# 7seg157.net
KiCad netlist of a schematic drawn in EAGLE
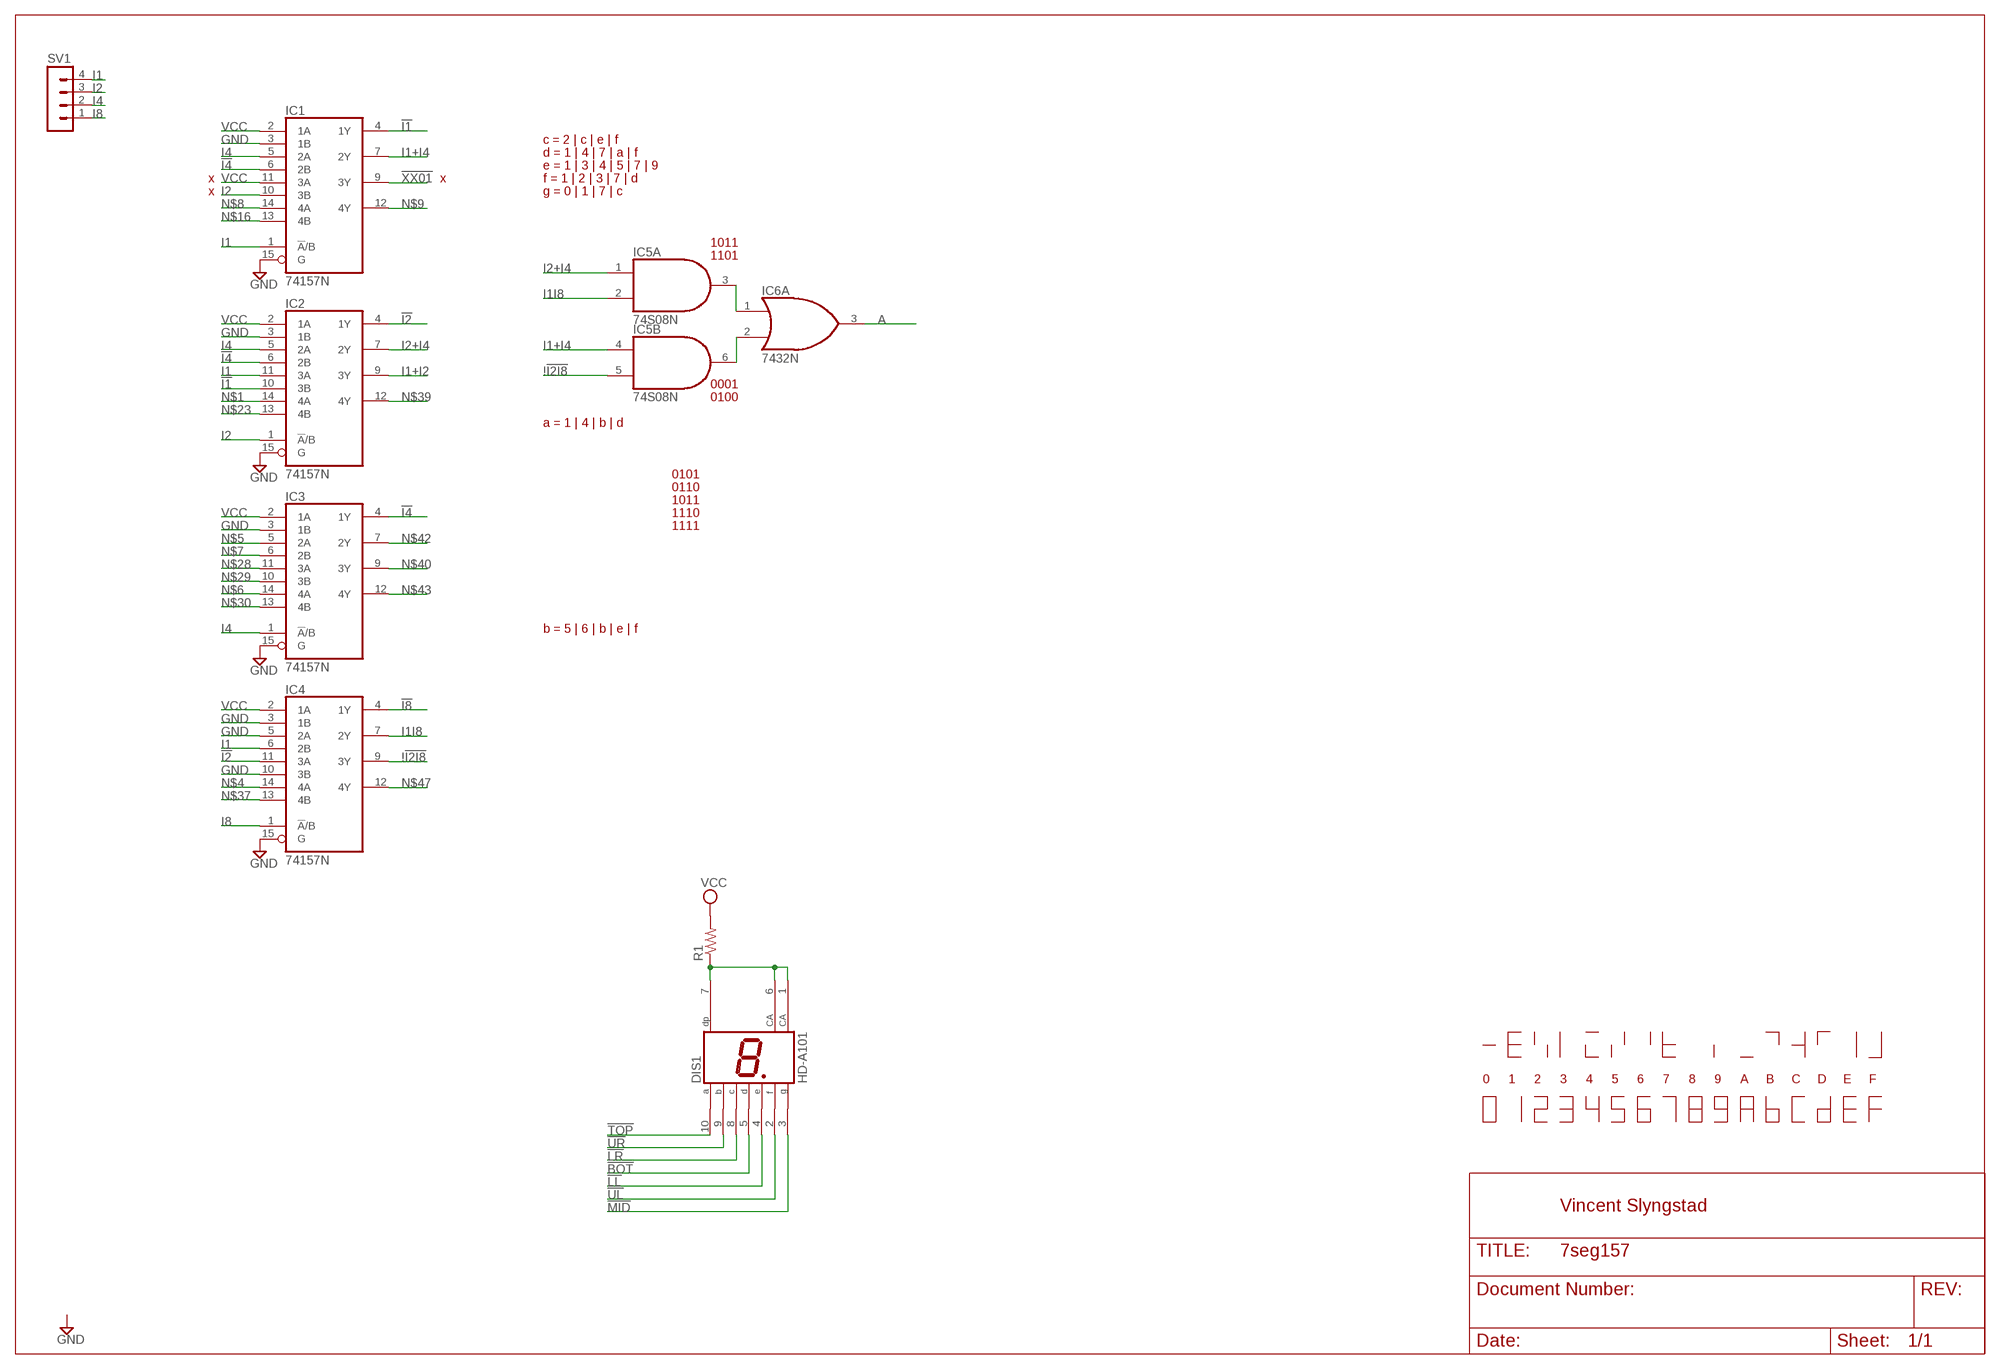
[diagram p0: schematic, sheet 1]

(export (version "E")
  (design (tool "Eeschema 10.0.6"))
  (components
    (comp (ref "DIS1")
      (value "HD-A101")
      (footprint "eagle-import:HDSP-A")
      (libsource (lib "eagle-import") (part "HD-A101"))
    )
    (comp (ref "IC1")
      (value "74157N")
      (footprint "eagle-import:DIL16")
      (libsource (lib "eagle-import") (part "74157N"))
    )
    (comp (ref "IC2")
      (value "74157N")
      (footprint "eagle-import:DIL16")
      (libsource (lib "eagle-import") (part "74157N"))
    )
    (comp (ref "IC3")
      (value "74157N")
      (footprint "eagle-import:DIL16")
      (libsource (lib "eagle-import") (part "74157N"))
    )
    (comp (ref "IC4")
      (value "74157N")
      (footprint "eagle-import:DIL16")
      (libsource (lib "eagle-import") (part "74157N"))
    )
    (comp (ref "IC5")
      (value "74S08N")
      (footprint "eagle-import:DIL14")
      (libsource (lib "eagle-import") (part "7408NS"))
    )
    (comp (ref "IC6")
      (value "7432N")
      (footprint "eagle-import:DIL14")
      (libsource (lib "eagle-import") (part "7432N"))
    )
    (comp (ref "R1")
      (value "R-US_0207/10")
      (footprint "eagle-import:0207_10")
      (libsource (lib "eagle-import") (part "R-US_0207/10"))
    )
    (comp (ref "SV1")
      (value "MA04-1")
      (footprint "eagle-import:MA04-1")
      (libsource (lib "eagle-import") (part "MA04-1"))
    )
  )
  (nets
    (net (code "1") (name "/A") (class "Default")
      (node (ref "IC6") (pin "3") (pinfunction "O_3") (pintype "output"))
    )
    (net (code "2") (name "/I1") (class "Default")
      (node (ref "IC1") (pin "1") (pinfunction "~{A}/B_1") (pintype "input"))
      (node (ref "IC2") (pin "11") (pinfunction "3A_11") (pintype "input"))
      (node (ref "IC4") (pin "6") (pinfunction "2B_6") (pintype "input"))
      (node (ref "SV1") (pin "4") (pinfunction "4_4") (pintype "passive"))
    )
    (net (code "3") (name "/I1+I2") (class "Default")
      (node (ref "IC2") (pin "9") (pinfunction "3Y_9") (pintype "output"))
    )
    (net (code "4") (name "/I1+I4") (class "Default")
      (node (ref "IC1") (pin "7") (pinfunction "2Y_7") (pintype "output"))
      (node (ref "IC5") (pin "4") (pinfunction "I0_4") (pintype "input"))
    )
    (net (code "5") (name "/I1I8") (class "Default")
      (node (ref "IC4") (pin "7") (pinfunction "2Y_7") (pintype "output"))
      (node (ref "IC5") (pin "2") (pinfunction "I1_2") (pintype "input"))
    )
    (net (code "6") (name "/I2") (class "Default")
      (node (ref "IC1") (pin "10") (pinfunction "3B_10") (pintype "input"))
      (node (ref "IC2") (pin "1") (pinfunction "~{A}/B_1") (pintype "input"))
      (node (ref "SV1") (pin "3") (pinfunction "3_3") (pintype "passive"))
    )
    (net (code "7") (name "/I2+I4") (class "Default")
      (node (ref "IC2") (pin "7") (pinfunction "2Y_7") (pintype "output"))
      (node (ref "IC5") (pin "1") (pinfunction "I0_1") (pintype "input"))
    )
    (net (code "8") (name "/I4") (class "Default")
      (node (ref "IC1") (pin "5") (pinfunction "2A_5") (pintype "input"))
      (node (ref "IC2") (pin "5") (pinfunction "2A_5") (pintype "input"))
      (node (ref "IC3") (pin "1") (pinfunction "~{A}/B_1") (pintype "input"))
      (node (ref "SV1") (pin "2") (pinfunction "2_2") (pintype "passive"))
    )
    (net (code "9") (name "/I8") (class "Default")
      (node (ref "IC4") (pin "1") (pinfunction "~{A}/B_1") (pintype "input"))
      (node (ref "SV1") (pin "1") (pinfunction "1_1") (pintype "passive"))
    )
    (net (code "10") (name "/N$1") (class "Default")
      (node (ref "IC2") (pin "14") (pinfunction "4A_14") (pintype "input"))
    )
    (net (code "11") (name "/N$4") (class "Default")
      (node (ref "IC4") (pin "14") (pinfunction "4A_14") (pintype "input"))
    )
    (net (code "12") (name "/N$5") (class "Default")
      (node (ref "IC3") (pin "5") (pinfunction "2A_5") (pintype "input"))
    )
    (net (code "13") (name "/N$6") (class "Default")
      (node (ref "IC3") (pin "14") (pinfunction "4A_14") (pintype "input"))
    )
    (net (code "14") (name "/N$7") (class "Default")
      (node (ref "IC3") (pin "6") (pinfunction "2B_6") (pintype "input"))
    )
    (net (code "15") (name "/N$8") (class "Default")
      (node (ref "IC1") (pin "14") (pinfunction "4A_14") (pintype "input"))
    )
    (net (code "16") (name "/N$9") (class "Default")
      (node (ref "IC1") (pin "12") (pinfunction "4Y_12") (pintype "output"))
    )
    (net (code "17") (name "/N$16") (class "Default")
      (node (ref "IC1") (pin "13") (pinfunction "4B_13") (pintype "input"))
    )
    (net (code "18") (name "/N$23") (class "Default")
      (node (ref "IC2") (pin "13") (pinfunction "4B_13") (pintype "input"))
    )
    (net (code "19") (name "/N$28") (class "Default")
      (node (ref "IC3") (pin "11") (pinfunction "3A_11") (pintype "input"))
    )
    (net (code "20") (name "/N$29") (class "Default")
      (node (ref "IC3") (pin "10") (pinfunction "3B_10") (pintype "input"))
    )
    (net (code "21") (name "/N$30") (class "Default")
      (node (ref "IC3") (pin "13") (pinfunction "4B_13") (pintype "input"))
    )
    (net (code "22") (name "/N$37") (class "Default")
      (node (ref "IC4") (pin "13") (pinfunction "4B_13") (pintype "input"))
    )
    (net (code "23") (name "/N$39") (class "Default")
      (node (ref "IC2") (pin "12") (pinfunction "4Y_12") (pintype "output"))
    )
    (net (code "24") (name "/N$40") (class "Default")
      (node (ref "IC3") (pin "9") (pinfunction "3Y_9") (pintype "output"))
    )
    (net (code "25") (name "/N$42") (class "Default")
      (node (ref "IC3") (pin "7") (pinfunction "2Y_7") (pintype "output"))
    )
    (net (code "26") (name "/N$43") (class "Default")
      (node (ref "IC3") (pin "12") (pinfunction "4Y_12") (pintype "output"))
    )
    (net (code "27") (name "/N$47") (class "Default")
      (node (ref "IC4") (pin "12") (pinfunction "4Y_12") (pintype "output"))
    )
    (net (code "28") (name "/~I2I8") (class "Default")
      (node (ref "IC4") (pin "9") (pinfunction "3Y_9") (pintype "output"))
      (node (ref "IC5") (pin "5") (pinfunction "I1_5") (pintype "input"))
    )
    (net (code "29") (name "/~{BOT}") (class "Default")
      (node (ref "DIS1") (pin "5") (pinfunction "D_5") (pintype "passive"))
    )
    (net (code "30") (name "/~{I1}") (class "Default")
      (node (ref "IC1") (pin "4") (pinfunction "1Y_4") (pintype "output"))
      (node (ref "IC2") (pin "10") (pinfunction "3B_10") (pintype "input"))
    )
    (net (code "31") (name "/~{I2}") (class "Default")
      (node (ref "IC2") (pin "4") (pinfunction "1Y_4") (pintype "output"))
      (node (ref "IC4") (pin "11") (pinfunction "3A_11") (pintype "input"))
    )
    (net (code "32") (name "/~{I4}") (class "Default")
      (node (ref "IC1") (pin "6") (pinfunction "2B_6") (pintype "input"))
      (node (ref "IC2") (pin "6") (pinfunction "2B_6") (pintype "input"))
      (node (ref "IC3") (pin "4") (pinfunction "1Y_4") (pintype "output"))
    )
    (net (code "33") (name "/~{I8}") (class "Default")
      (node (ref "IC4") (pin "4") (pinfunction "1Y_4") (pintype "output"))
    )
    (net (code "34") (name "/~{LL}") (class "Default")
      (node (ref "DIS1") (pin "4") (pinfunction "E_4") (pintype "passive"))
    )
    (net (code "35") (name "/~{LR}") (class "Default")
      (node (ref "DIS1") (pin "8") (pinfunction "C_8") (pintype "passive"))
    )
    (net (code "36") (name "/~{MID}") (class "Default")
      (node (ref "DIS1") (pin "3") (pinfunction "G_3") (pintype "passive"))
    )
    (net (code "37") (name "/~{TOP}") (class "Default")
      (node (ref "DIS1") (pin "10") (pinfunction "A_10") (pintype "passive"))
    )
    (net (code "38") (name "/~{UL}") (class "Default")
      (node (ref "DIS1") (pin "2") (pinfunction "F_2") (pintype "passive"))
    )
    (net (code "39") (name "/~{UR}") (class "Default")
      (node (ref "DIS1") (pin "9") (pinfunction "B_9") (pintype "passive"))
    )
    (net (code "40") (name "/~{XX01}") (class "Default")
      (node (ref "IC1") (pin "9") (pinfunction "3Y_9") (pintype "output"))
    )
    (net (code "41") (name "GND") (class "Default")
      (node (ref "IC1") (pin "15") (pinfunction "G_15") (pintype "input"))
      (node (ref "IC1") (pin "3") (pinfunction "1B_3") (pintype "input"))
      (node (ref "IC2") (pin "15") (pinfunction "G_15") (pintype "input"))
      (node (ref "IC2") (pin "3") (pinfunction "1B_3") (pintype "input"))
      (node (ref "IC3") (pin "15") (pinfunction "G_15") (pintype "input"))
      (node (ref "IC3") (pin "3") (pinfunction "1B_3") (pintype "input"))
      (node (ref "IC4") (pin "10") (pinfunction "3B_10") (pintype "input"))
      (node (ref "IC4") (pin "15") (pinfunction "G_15") (pintype "input"))
      (node (ref "IC4") (pin "3") (pinfunction "1B_3") (pintype "input"))
      (node (ref "IC4") (pin "5") (pinfunction "2A_5") (pintype "input"))
    )
    (net (code "42") (name "Net-(DIS1-DP)") (class "Default")
      (node (ref "DIS1") (pin "1") (pinfunction "CA_1") (pintype "passive"))
      (node (ref "DIS1") (pin "6") (pinfunction "CA_6") (pintype "passive"))
      (node (ref "DIS1") (pin "7") (pinfunction "DP_7") (pintype "passive"))
      (node (ref "R1") (pin "1") (pinfunction "1_1") (pintype "passive"))
    )
    (net (code "43") (name "Net-(IC5A-O)") (class "Default")
      (node (ref "IC5") (pin "3") (pinfunction "O_3") (pintype "output"))
      (node (ref "IC6") (pin "1") (pinfunction "I0_1") (pintype "input"))
    )
    (net (code "44") (name "Net-(IC5B-O)") (class "Default")
      (node (ref "IC5") (pin "6") (pinfunction "O_6") (pintype "output"))
      (node (ref "IC6") (pin "2") (pinfunction "I1_2") (pintype "input"))
    )
    (net (code "45") (name "VCC") (class "Default")
      (node (ref "IC1") (pin "11") (pinfunction "3A_11") (pintype "input"))
      (node (ref "IC1") (pin "2") (pinfunction "1A_2") (pintype "input"))
      (node (ref "IC2") (pin "2") (pinfunction "1A_2") (pintype "input"))
      (node (ref "IC3") (pin "2") (pinfunction "1A_2") (pintype "input"))
      (node (ref "IC4") (pin "2") (pinfunction "1A_2") (pintype "input"))
      (node (ref "R1") (pin "2") (pinfunction "2_2") (pintype "passive"))
    )
  )
)
